# Total.net
KiCad netlist of a schematic drawn in Altium Designer
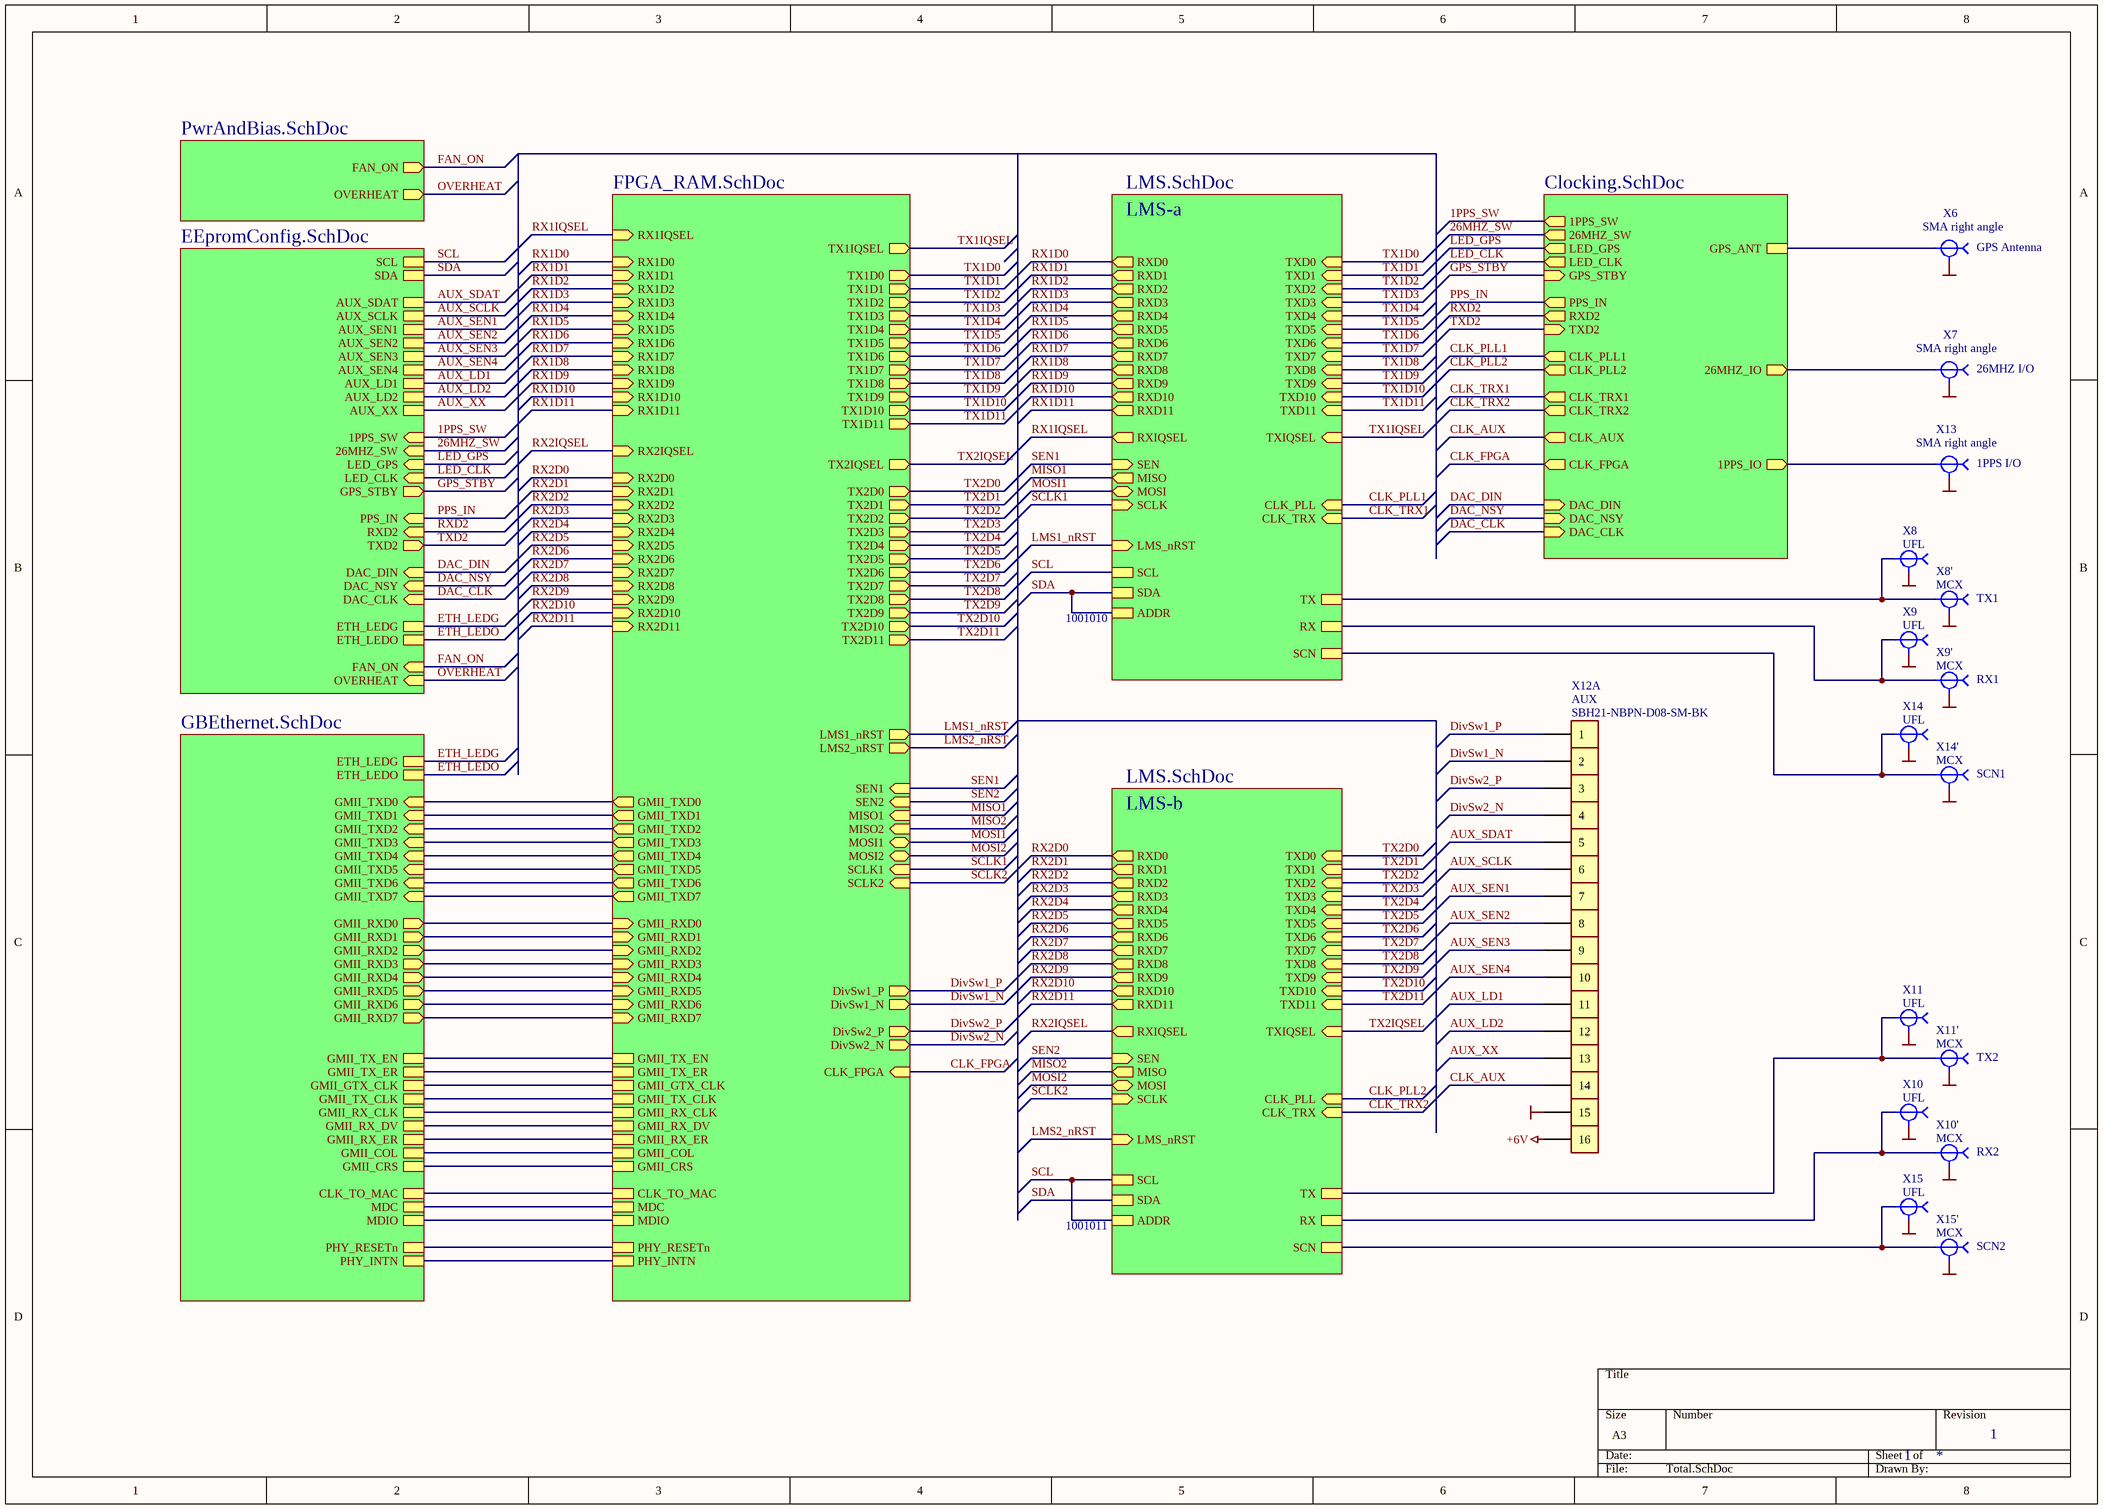
[diagram p0: Total.SchDoc]

(export (version "E")
  (design (tool "Eeschema 10.0.6"))
  (components
    (comp (ref "X6")
      (value "SMA right angle")
      (footprint "SMA right angle")
      (description "GPS Antenna")
      (libsource (lib "Andy") (part "SMA-Right Angle"))
    )
    (comp (ref "X7")
      (value "SMA right angle")
      (footprint "SMA right angle")
      (description "26MHZ I/O")
      (libsource (lib "Andy") (part "SMA-Right Angle"))
    )
    (comp (ref "X8")
      (value "UFL")
      (footprint "U_FL")
      (description "Ultraminiature Coax Connector (UMCC)")
      (fields (field (name "MANUFACTURER") "Tyco Electronics Corp"))
      (libsource (lib "Andy") (part "U_FL"))
    )
    (comp (ref "X8'")
      (value "MCX")
      (footprint "ML 120")
      (fields (field (name "MANUFACTURER") "Tyco Electronics Corp") (field (name "DISCRIPTION") "TX1"))
      (libsource (lib "Andy") (part "MCX SM"))
    )
    (comp (ref "X9")
      (value "UFL")
      (footprint "U_FL")
      (description "Ultraminiature Coax Connector (UMCC)")
      (fields (field (name "MANUFACTURER") "Tyco Electronics Corp"))
      (libsource (lib "Andy") (part "U_FL"))
    )
    (comp (ref "X9'")
      (value "MCX")
      (footprint "ML 120")
      (fields (field (name "MANUFACTURER") "Tyco Electronics Corp") (field (name "DISCRIPTION") "RX1"))
      (libsource (lib "Andy") (part "MCX SM"))
    )
    (comp (ref "X10")
      (value "UFL")
      (footprint "U_FL")
      (description "Ultraminiature Coax Connector (UMCC)")
      (fields (field (name "MANUFACTURER") "Tyco Electronics Corp"))
      (libsource (lib "Andy") (part "U_FL"))
    )
    (comp (ref "X10'")
      (value "MCX")
      (footprint "ML 120")
      (fields (field (name "MANUFACTURER") "Tyco Electronics Corp") (field (name "DISCRIPTION") "RX2"))
      (libsource (lib "Andy") (part "MCX SM"))
    )
    (comp (ref "X11")
      (value "UFL")
      (footprint "U_FL")
      (description "Ultraminiature Coax Connector (UMCC)")
      (fields (field (name "MANUFACTURER") "Tyco Electronics Corp"))
      (libsource (lib "Andy") (part "U_FL"))
    )
    (comp (ref "X11'")
      (value "MCX")
      (footprint "ML 120")
      (fields (field (name "MANUFACTURER") "Tyco Electronics Corp") (field (name "DISCRIPTION") "TX2"))
      (libsource (lib "Andy") (part "MCX SM"))
    )
    (comp (ref "X12")
      (value "SBH21-NBPN-D08-SM-BK")
      (footprint "SBH-16")
      (description "Connector 2mm SMD")
      (fields (field (name "MANUFACTURER") "Sullins") (field (name "MISC") "AUX"))
      (libsource (lib "Andy") (part "SBH21-8x2_SMD"))
    )
    (comp (ref "X13")
      (value "SMA right angle")
      (footprint "SMA right angle")
      (description "1PPS I/O")
      (libsource (lib "Andy") (part "SMA-Right Angle"))
    )
    (comp (ref "X14")
      (value "UFL")
      (footprint "U_FL")
      (description "Ultraminiature Coax Connector (UMCC)")
      (fields (field (name "MANUFACTURER") "Tyco Electronics Corp"))
      (libsource (lib "Andy") (part "U_FL"))
    )
    (comp (ref "X14'")
      (value "MCX")
      (footprint "ML 120")
      (fields (field (name "MANUFACTURER") "Tyco Electronics Corp") (field (name "DISCRIPTION") "SCN1"))
      (libsource (lib "Andy") (part "MCX SM"))
    )
    (comp (ref "X15")
      (value "UFL")
      (footprint "U_FL")
      (description "Ultraminiature Coax Connector (UMCC)")
      (fields (field (name "MANUFACTURER") "Tyco Electronics Corp"))
      (libsource (lib "Andy") (part "U_FL"))
    )
    (comp (ref "X15'")
      (value "MCX")
      (footprint "ML 120")
      (fields (field (name "MANUFACTURER") "Tyco Electronics Corp") (field (name "DISCRIPTION") "SCN2"))
      (libsource (lib "Andy") (part "MCX SM"))
    )
  )
  (nets
    (net (code "1") (name "+6V") (class "Default")
      (node (ref "X12") (pin "16") (pinfunction "16_16") (pintype "passive"))
    )
    (net (code "2") (name "/1PPS_IO") (class "Default")
      (node (ref "X13") (pin "1") (pinfunction "1_1") (pintype "passive"))
    )
    (net (code "4") (name "/26MHZ_IO") (class "Default")
      (node (ref "X7") (pin "1") (pinfunction "1_1") (pintype "passive"))
    )
    (net (code "6") (name "/AUX_LD1") (class "Default")
      (node (ref "X12") (pin "11") (pinfunction "11_11") (pintype "passive"))
    )
    (net (code "7") (name "/AUX_LD2") (class "Default")
      (node (ref "X12") (pin "12") (pinfunction "12_12") (pintype "passive"))
    )
    (net (code "8") (name "/AUX_SCLK") (class "Default")
      (node (ref "X12") (pin "6") (pinfunction "6_6") (pintype "passive"))
    )
    (net (code "9") (name "/AUX_SDAT") (class "Default")
      (node (ref "X12") (pin "5") (pinfunction "5_5") (pintype "passive"))
    )
    (net (code "10") (name "/AUX_SEN1") (class "Default")
      (node (ref "X12") (pin "7") (pinfunction "7_7") (pintype "passive"))
    )
    (net (code "11") (name "/AUX_SEN2") (class "Default")
      (node (ref "X12") (pin "8") (pinfunction "8_8") (pintype "passive"))
    )
    (net (code "12") (name "/AUX_SEN3") (class "Default")
      (node (ref "X12") (pin "9") (pinfunction "9_9") (pintype "passive"))
    )
    (net (code "13") (name "/AUX_SEN4") (class "Default")
      (node (ref "X12") (pin "10") (pinfunction "10_10") (pintype "passive"))
    )
    (net (code "14") (name "/AUX_XX") (class "Default")
      (node (ref "X12") (pin "13") (pinfunction "13_13") (pintype "passive"))
    )
    (net (code "15") (name "/CLK_AUX") (class "Default")
      (node (ref "X12") (pin "14") (pinfunction "14_14") (pintype "passive"))
    )
    (net (code "25") (name "/DivSw1_N") (class "Default")
      (node (ref "X12") (pin "2") (pinfunction "2_2") (pintype "passive"))
    )
    (net (code "26") (name "/DivSw1_P") (class "Default")
      (node (ref "X12") (pin "1") (pinfunction "1_1") (pintype "passive"))
    )
    (net (code "27") (name "/DivSw2_N") (class "Default")
      (node (ref "X12") (pin "4") (pinfunction "4_4") (pintype "passive"))
    )
    (net (code "28") (name "/DivSw2_P") (class "Default")
      (node (ref "X12") (pin "3") (pinfunction "3_3") (pintype "passive"))
    )
    (net (code "57") (name "/GPS_ANT") (class "Default")
      (node (ref "X6") (pin "1") (pinfunction "1_1") (pintype "passive"))
    )
    (net (code "73") (name "/RX") (class "Default")
      (node (ref "X9") (pin "1") (pinfunction "1_1") (pintype "passive"))
      (node (ref "X9'") (pin "1") (pinfunction "1_1") (pintype "passive"))
    )
    (net (code "101") (name "/RX_1") (class "Default")
      (node (ref "X10") (pin "1") (pinfunction "1_1") (pintype "passive"))
      (node (ref "X10'") (pin "1") (pinfunction "1_1") (pintype "passive"))
    )
    (net (code "105") (name "/SCN") (class "Default")
      (node (ref "X14") (pin "1") (pinfunction "1_1") (pintype "passive"))
      (node (ref "X14'") (pin "1") (pinfunction "1_1") (pintype "passive"))
    )
    (net (code "106") (name "/SCN_1") (class "Default")
      (node (ref "X15") (pin "1") (pinfunction "1_1") (pintype "passive"))
      (node (ref "X15'") (pin "1") (pinfunction "1_1") (pintype "passive"))
    )
    (net (code "110") (name "/TX") (class "Default")
      (node (ref "X8") (pin "1") (pinfunction "1_1") (pintype "passive"))
      (node (ref "X8'") (pin "1") (pinfunction "1_1") (pintype "passive"))
    )
    (net (code "138") (name "/TX_1") (class "Default")
      (node (ref "X11") (pin "1") (pinfunction "1_1") (pintype "passive"))
      (node (ref "X11'") (pin "1") (pinfunction "1_1") (pintype "passive"))
    )
    (net (code "139") (name "GND") (class "Default")
      (node (ref "X10") (pin "2") (pinfunction "GND_2") (pintype "passive"))
      (node (ref "X10'") (pin "2") (pinfunction "GND_2") (pintype "passive"))
      (node (ref "X11") (pin "2") (pinfunction "GND_2") (pintype "passive"))
      (node (ref "X11'") (pin "2") (pinfunction "GND_2") (pintype "passive"))
      (node (ref "X12") (pin "15") (pinfunction "15_15") (pintype "passive"))
      (node (ref "X13") (pin "2") (pinfunction "GND_2") (pintype "power_in"))
      (node (ref "X14") (pin "2") (pinfunction "GND_2") (pintype "passive"))
      (node (ref "X14'") (pin "2") (pinfunction "GND_2") (pintype "passive"))
      (node (ref "X15") (pin "2") (pinfunction "GND_2") (pintype "passive"))
      (node (ref "X15'") (pin "2") (pinfunction "GND_2") (pintype "passive"))
      (node (ref "X6") (pin "2") (pinfunction "GND_2") (pintype "power_in"))
      (node (ref "X7") (pin "2") (pinfunction "GND_2") (pintype "power_in"))
      (node (ref "X8") (pin "2") (pinfunction "GND_2") (pintype "passive"))
      (node (ref "X8'") (pin "2") (pinfunction "GND_2") (pintype "passive"))
      (node (ref "X9") (pin "2") (pinfunction "GND_2") (pintype "passive"))
      (node (ref "X9'") (pin "2") (pinfunction "GND_2") (pintype "passive"))
    )
  )
)
